# t4_ega_vga.net
KiCad netlist of a schematic drawn in EAGLE
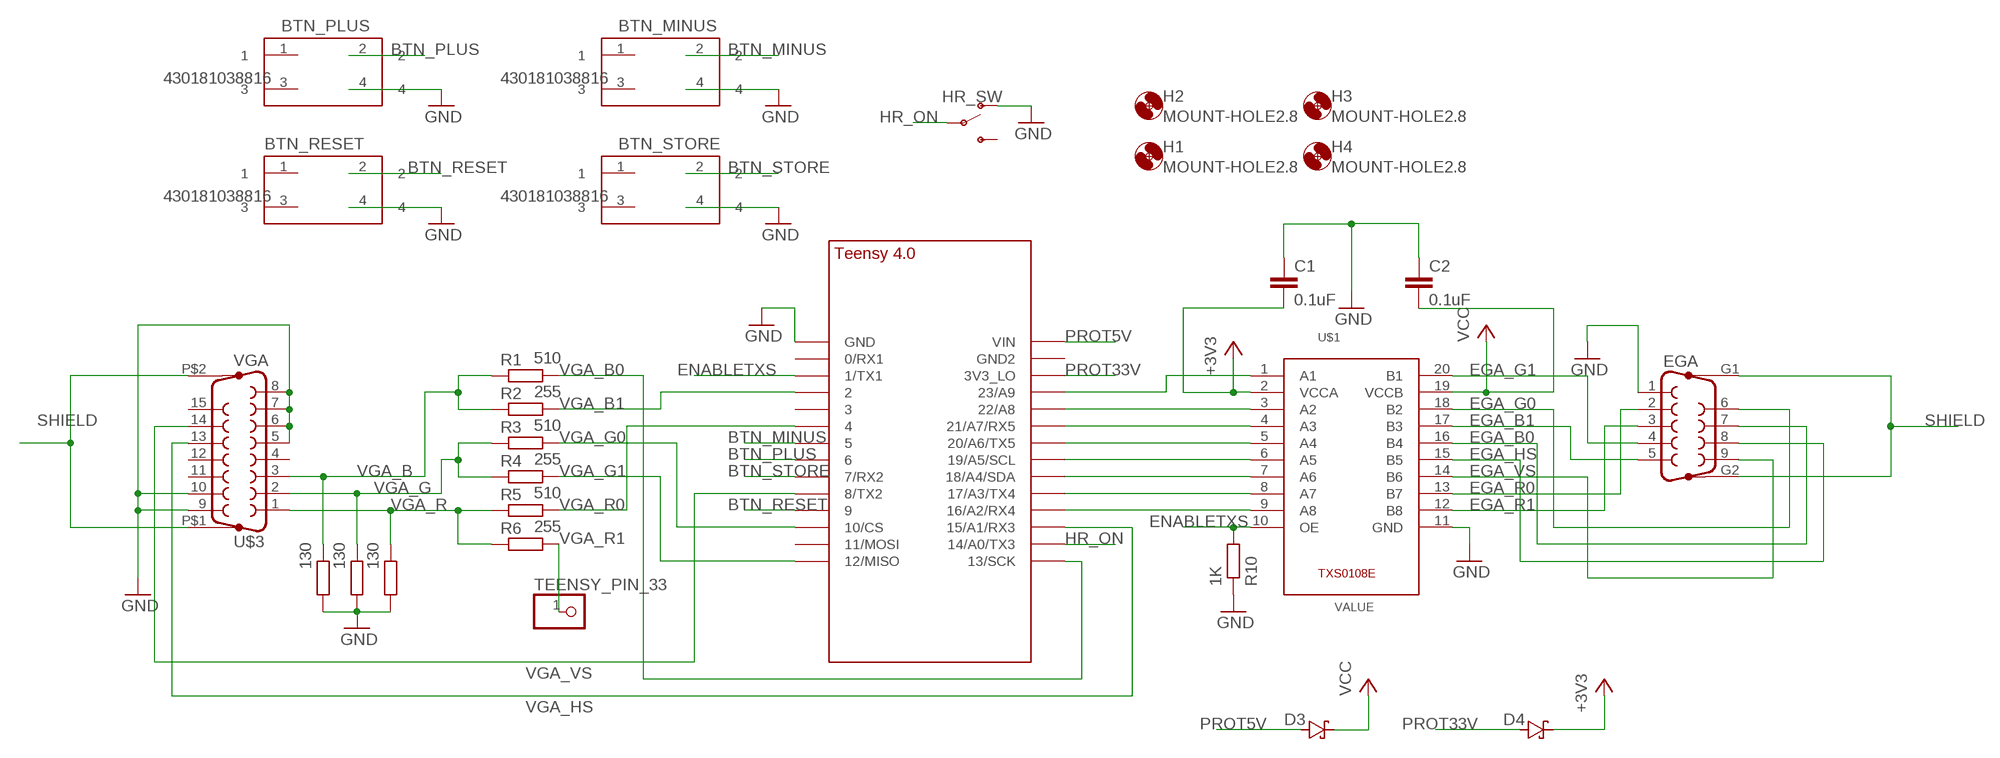
[diagram p0: schematic, sheet 1]

(export (version "E")
  (design (tool "Eeschema 10.0.6"))
  (components
    (comp (ref "BTN_MINUS")
      (value "430181038816")
      (footprint "eagle-import:430181038816")
      (libsource (lib "eagle-import") (part "430181038816"))
    )
    (comp (ref "BTN_PLUS")
      (value "430181038816")
      (footprint "eagle-import:430181038816")
      (libsource (lib "eagle-import") (part "430181038816"))
    )
    (comp (ref "BTN_RESET")
      (value "430181038816")
      (footprint "eagle-import:430181038816")
      (libsource (lib "eagle-import") (part "430181038816"))
    )
    (comp (ref "BTN_STORE")
      (value "430181038816")
      (footprint "eagle-import:430181038816")
      (libsource (lib "eagle-import") (part "430181038816"))
    )
    (comp (ref "C1")
      (value "0.1uF")
      (footprint "eagle-import:C0603")
      (libsource (lib "eagle-import") (part "C-EUC0603"))
    )
    (comp (ref "C2")
      (value "0.1uF")
      (footprint "eagle-import:C0603")
      (libsource (lib "eagle-import") (part "C-EUC0603"))
    )
    (comp (ref "D3")
      (value "SMA-SS34-SYMBOL")
      (footprint "eagle-import:SMA-SS34")
      (libsource (lib "eagle-import") (part "SMA-SS34-SYMBOL"))
    )
    (comp (ref "D4")
      (value "SMA-SS34-SYMBOL")
      (footprint "eagle-import:SMA-SS34")
      (libsource (lib "eagle-import") (part "SMA-SS34-SYMBOL"))
    )
    (comp (ref "EGA")
      (value "F09HP")
      (footprint "eagle-import:F09HP")
      (libsource (lib "eagle-import") (part "F09HP"))
    )
    (comp (ref "H1")
      (value "MOUNT-HOLE2.8")
      (footprint "eagle-import:2,8")
      (libsource (lib "eagle-import") (part "MOUNT-HOLE2.8"))
    )
    (comp (ref "H2")
      (value "MOUNT-HOLE2.8")
      (footprint "eagle-import:2,8")
      (libsource (lib "eagle-import") (part "MOUNT-HOLE2.8"))
    )
    (comp (ref "H3")
      (value "MOUNT-HOLE2.8")
      (footprint "eagle-import:2,8")
      (libsource (lib "eagle-import") (part "MOUNT-HOLE2.8"))
    )
    (comp (ref "H4")
      (value "MOUNT-HOLE2.8")
      (footprint "eagle-import:2,8")
      (libsource (lib "eagle-import") (part "MOUNT-HOLE2.8"))
    )
    (comp (ref "HR_SW")
      (value "SWITCH-SPDT-SMD-RIGHT-ANGLE")
      (footprint "eagle-import:SWITCH_SPST_SMD_A")
      (libsource (lib "eagle-import") (part "SWITCH-SPDT-SMD-RIGHT-ANGLE"))
    )
    (comp (ref "R1")
      (value "510")
      (footprint "eagle-import:R0603")
      (libsource (lib "eagle-import") (part "R-EU_R0603"))
    )
    (comp (ref "R2")
      (value "255")
      (footprint "eagle-import:R0603")
      (libsource (lib "eagle-import") (part "R-EU_R0603"))
    )
    (comp (ref "R3")
      (value "510")
      (footprint "eagle-import:R0603")
      (libsource (lib "eagle-import") (part "R-EU_R0603"))
    )
    (comp (ref "R4")
      (value "255")
      (footprint "eagle-import:R0603")
      (libsource (lib "eagle-import") (part "R-EU_R0603"))
    )
    (comp (ref "R5")
      (value "510")
      (footprint "eagle-import:R0603")
      (libsource (lib "eagle-import") (part "R-EU_R0603"))
    )
    (comp (ref "R6")
      (value "255")
      (footprint "eagle-import:R0603")
      (libsource (lib "eagle-import") (part "R-EU_R0603"))
    )
    (comp (ref "R7")
      (value "130")
      (footprint "eagle-import:R0603")
      (libsource (lib "eagle-import") (part "R-EU_R0603"))
    )
    (comp (ref "R8")
      (value "130")
      (footprint "eagle-import:R0603")
      (libsource (lib "eagle-import") (part "R-EU_R0603"))
    )
    (comp (ref "R9")
      (value "130")
      (footprint "eagle-import:R0603")
      (libsource (lib "eagle-import") (part "R-EU_R0603"))
    )
    (comp (ref "R10")
      (value "1K")
      (footprint "eagle-import:R0603")
      (libsource (lib "eagle-import") (part "R-EU_R0603"))
    )
    (comp (ref "TEENSY_PIN_33")
      (value "PINHD-1X1")
      (footprint "eagle-import:1X01")
      (libsource (lib "eagle-import") (part "PINHD-1X1"))
    )
    (comp (ref "U$1")
      (value "TXS0108E")
      (footprint "eagle-import:TSSOP20")
      (libsource (lib "eagle-import") (part "TXS0108E"))
    )
    (comp (ref "U$3")
      (value "VGA")
      (footprint "eagle-import:HDF15H")
      (libsource (lib "eagle-import") (part "VGA"))
    )
    (comp (ref "U2")
      (value "TEENSY_4.0-BASIC")
      (footprint "eagle-import:TEENSY_4.0-BASIC")
      (libsource (lib "eagle-import") (part "TEENSY_4.0-BASIC"))
    )
  )
  (nets
    (net (code "1") (name "+3V3") (class "Default")
      (node (ref "C1") (pin "2") (pinfunction "2_2") (pintype "passive"))
      (node (ref "D4") (pin "2") (pinfunction "K_2") (pintype "passive"))
      (node (ref "U$1") (pin "2") (pinfunction "VCCA_2") (pintype "bidirectional"))
    )
    (net (code "2") (name "/BTN_MINUS") (class "Default")
      (node (ref "BTN_MINUS") (pin "2") (pinfunction "2_2") (pintype "bidirectional"))
      (node (ref "U2") (pin "5") (pinfunction "5_5") (pintype "bidirectional"))
    )
    (net (code "3") (name "/BTN_PLUS") (class "Default")
      (node (ref "BTN_PLUS") (pin "2") (pinfunction "2_2") (pintype "bidirectional"))
      (node (ref "U2") (pin "6") (pinfunction "6_6") (pintype "bidirectional"))
    )
    (net (code "4") (name "/BTN_RESET") (class "Default")
      (node (ref "BTN_RESET") (pin "2") (pinfunction "2_2") (pintype "bidirectional"))
      (node (ref "U2") (pin "9/CS") (pinfunction "9_9/CS") (pintype "bidirectional"))
    )
    (net (code "5") (name "/BTN_STORE") (class "Default")
      (node (ref "BTN_STORE") (pin "2") (pinfunction "2_2") (pintype "bidirectional"))
      (node (ref "U2") (pin "7") (pinfunction "7/RX2_7") (pintype "bidirectional"))
    )
    (net (code "6") (name "/EGA_B0") (class "Default")
      (node (ref "EGA") (pin "7") (pinfunction "7_7") (pintype "passive"))
      (node (ref "U$1") (pin "16") (pinfunction "B4_16") (pintype "bidirectional"))
    )
    (net (code "7") (name "/EGA_B1") (class "Default")
      (node (ref "EGA") (pin "5") (pinfunction "5_5") (pintype "passive"))
      (node (ref "U$1") (pin "17") (pinfunction "B3_17") (pintype "bidirectional"))
    )
    (net (code "8") (name "/EGA_G0") (class "Default")
      (node (ref "EGA") (pin "6") (pinfunction "6_6") (pintype "passive"))
      (node (ref "U$1") (pin "18") (pinfunction "B2_18") (pintype "bidirectional"))
    )
    (net (code "9") (name "/EGA_G1") (class "Default")
      (node (ref "EGA") (pin "4") (pinfunction "4_4") (pintype "passive"))
      (node (ref "U$1") (pin "20") (pinfunction "B1_20") (pintype "bidirectional"))
    )
    (net (code "10") (name "/EGA_HS") (class "Default")
      (node (ref "EGA") (pin "8") (pinfunction "8_8") (pintype "passive"))
      (node (ref "U$1") (pin "15") (pinfunction "B5_15") (pintype "bidirectional"))
    )
    (net (code "11") (name "/EGA_R0") (class "Default")
      (node (ref "EGA") (pin "2") (pinfunction "2_2") (pintype "passive"))
      (node (ref "U$1") (pin "13") (pinfunction "B7_13") (pintype "bidirectional"))
    )
    (net (code "12") (name "/EGA_R1") (class "Default")
      (node (ref "EGA") (pin "3") (pinfunction "3_3") (pintype "passive"))
      (node (ref "U$1") (pin "12") (pinfunction "B8_12") (pintype "bidirectional"))
    )
    (net (code "13") (name "/EGA_VS") (class "Default")
      (node (ref "EGA") (pin "9") (pinfunction "9_9") (pintype "passive"))
      (node (ref "U$1") (pin "14") (pinfunction "B6_14") (pintype "bidirectional"))
    )
    (net (code "14") (name "/ENABLETXS") (class "Default")
      (node (ref "R10") (pin "2") (pinfunction "2_2") (pintype "passive"))
      (node (ref "U$1") (pin "10") (pinfunction "OE_10") (pintype "bidirectional"))
      (node (ref "U2") (pin "1/TX") (pinfunction "1/TX1_1/TX") (pintype "bidirectional"))
    )
    (net (code "15") (name "/HR_ON") (class "Default")
      (node (ref "HR_SW") (pin "2") (pinfunction "P_2") (pintype "passive"))
      (node (ref "U2") (pin "14/A0") (pinfunction "14/A0/TX3_14/A0") (pintype "bidirectional"))
    )
    (net (code "16") (name "/PROT5V") (class "Default")
      (node (ref "D3") (pin "1") (pinfunction "A_1") (pintype "passive"))
      (node (ref "U2") (pin "VIN") (pinfunction "VIN_VIN") (pintype "bidirectional"))
    )
    (net (code "17") (name "/PROT33V") (class "Default")
      (node (ref "D4") (pin "1") (pinfunction "A_1") (pintype "passive"))
      (node (ref "U2") (pin "3V3_LO") (pinfunction "3V3_LO_3V3_LO") (pintype "bidirectional"))
    )
    (net (code "18") (name "/SHIELD") (class "Default")
      (node (ref "EGA") (pin "G1") (pinfunction "G1_G1") (pintype "passive"))
      (node (ref "EGA") (pin "G2") (pinfunction "G2_G2") (pintype "passive"))
      (node (ref "U$3") (pin "P$1") (pinfunction "G1_P$1") (pintype "passive"))
      (node (ref "U$3") (pin "P$2") (pinfunction "G2_P$2") (pintype "passive"))
    )
    (net (code "19") (name "/VGA_B") (class "Default")
      (node (ref "R1") (pin "1") (pinfunction "1_1") (pintype "passive"))
      (node (ref "R2") (pin "1") (pinfunction "1_1") (pintype "passive"))
      (node (ref "R7") (pin "2") (pinfunction "2_2") (pintype "passive"))
      (node (ref "U$3") (pin "3") (pinfunction "3_3") (pintype "passive"))
    )
    (net (code "20") (name "/VGA_B0") (class "Default")
      (node (ref "R1") (pin "2") (pinfunction "2_2") (pintype "passive"))
      (node (ref "U2") (pin "13/SCK") (pinfunction "13/SCK_13/SCK") (pintype "bidirectional"))
    )
    (net (code "21") (name "/VGA_B1") (class "Default")
      (node (ref "R2") (pin "2") (pinfunction "2_2") (pintype "passive"))
      (node (ref "U2") (pin "2") (pinfunction "2_2") (pintype "bidirectional"))
    )
    (net (code "22") (name "/VGA_G") (class "Default")
      (node (ref "R3") (pin "1") (pinfunction "1_1") (pintype "passive"))
      (node (ref "R4") (pin "1") (pinfunction "1_1") (pintype "passive"))
      (node (ref "R8") (pin "2") (pinfunction "2_2") (pintype "passive"))
      (node (ref "U$3") (pin "2") (pinfunction "2_2") (pintype "passive"))
    )
    (net (code "23") (name "/VGA_G0") (class "Default")
      (node (ref "R3") (pin "2") (pinfunction "2_2") (pintype "passive"))
      (node (ref "U2") (pin "10/CS") (pinfunction "10/CS_10/CS") (pintype "bidirectional"))
    )
    (net (code "24") (name "/VGA_G1") (class "Default")
      (node (ref "R4") (pin "2") (pinfunction "2_2") (pintype "passive"))
      (node (ref "U2") (pin "12/MISO") (pinfunction "12/MISO_12/MISO") (pintype "bidirectional"))
    )
    (net (code "25") (name "/VGA_HS") (class "Default")
      (node (ref "U$3") (pin "13") (pinfunction "13_13") (pintype "passive"))
      (node (ref "U2") (pin "15/A1") (pinfunction "15/A1/RX3_15/A1") (pintype "bidirectional"))
    )
    (net (code "26") (name "/VGA_R") (class "Default")
      (node (ref "R5") (pin "1") (pinfunction "1_1") (pintype "passive"))
      (node (ref "R6") (pin "1") (pinfunction "1_1") (pintype "passive"))
      (node (ref "R9") (pin "2") (pinfunction "2_2") (pintype "passive"))
      (node (ref "U$3") (pin "1") (pinfunction "1_1") (pintype "passive"))
    )
    (net (code "27") (name "/VGA_R0") (class "Default")
      (node (ref "R5") (pin "2") (pinfunction "2_2") (pintype "passive"))
      (node (ref "U2") (pin "4/CANRX") (pinfunction "4_4/CANRX") (pintype "bidirectional"))
    )
    (net (code "28") (name "/VGA_R1") (class "Default")
      (node (ref "R6") (pin "2") (pinfunction "2_2") (pintype "passive"))
      (node (ref "TEENSY_PIN_33") (pin "1") (pinfunction "1_1") (pintype "passive"))
    )
    (net (code "29") (name "/VGA_VS") (class "Default")
      (node (ref "U$3") (pin "14") (pinfunction "14_14") (pintype "passive"))
      (node (ref "U2") (pin "8") (pinfunction "8/TX2_8") (pintype "bidirectional"))
    )
    (net (code "30") (name "GND") (class "Default")
      (node (ref "BTN_MINUS") (pin "4") (pinfunction "4_4") (pintype "bidirectional"))
      (node (ref "BTN_PLUS") (pin "4") (pinfunction "4_4") (pintype "bidirectional"))
      (node (ref "BTN_RESET") (pin "4") (pinfunction "4_4") (pintype "bidirectional"))
      (node (ref "BTN_STORE") (pin "4") (pinfunction "4_4") (pintype "bidirectional"))
      (node (ref "C1") (pin "1") (pinfunction "1_1") (pintype "passive"))
      (node (ref "C2") (pin "1") (pinfunction "1_1") (pintype "passive"))
      (node (ref "EGA") (pin "1") (pinfunction "1_1") (pintype "passive"))
      (node (ref "HR_SW") (pin "1") (pinfunction "O_1") (pintype "passive"))
      (node (ref "R10") (pin "1") (pinfunction "1_1") (pintype "passive"))
      (node (ref "R7") (pin "1") (pinfunction "1_1") (pintype "passive"))
      (node (ref "R8") (pin "1") (pinfunction "1_1") (pintype "passive"))
      (node (ref "R9") (pin "1") (pinfunction "1_1") (pintype "passive"))
      (node (ref "U$1") (pin "11") (pinfunction "GND_11") (pintype "bidirectional"))
      (node (ref "U$3") (pin "10") (pinfunction "10_10") (pintype "passive"))
      (node (ref "U$3") (pin "5") (pinfunction "5_5") (pintype "passive"))
      (node (ref "U$3") (pin "6") (pinfunction "6_6") (pintype "passive"))
      (node (ref "U$3") (pin "7") (pinfunction "7_7") (pintype "passive"))
      (node (ref "U$3") (pin "8") (pinfunction "8_8") (pintype "passive"))
      (node (ref "U$3") (pin "9") (pinfunction "9_9") (pintype "passive"))
      (node (ref "U2") (pin "GND") (pinfunction "GND_GND") (pintype "bidirectional"))
    )
    (net (code "31") (name "Net-(U$1-A1)") (class "Default")
      (node (ref "U$1") (pin "1") (pinfunction "A1_1") (pintype "bidirectional"))
      (node (ref "U2") (pin "23/A9") (pinfunction "23/A9_23/A9") (pintype "bidirectional"))
    )
    (net (code "32") (name "Net-(U$1-A2)") (class "Default")
      (node (ref "U$1") (pin "3") (pinfunction "A2_3") (pintype "bidirectional"))
      (node (ref "U2") (pin "22/A8") (pinfunction "22/A8_22/A8") (pintype "bidirectional"))
    )
    (net (code "33") (name "Net-(U$1-A3)") (class "Default")
      (node (ref "U$1") (pin "4") (pinfunction "A3_4") (pintype "bidirectional"))
      (node (ref "U2") (pin "21/A7") (pinfunction "21/A7/RX5_21/A7") (pintype "bidirectional"))
    )
    (net (code "34") (name "Net-(U$1-A4)") (class "Default")
      (node (ref "U$1") (pin "5") (pinfunction "A4_5") (pintype "bidirectional"))
      (node (ref "U2") (pin "20/A6") (pinfunction "20/A6/TX5_20/A6") (pintype "bidirectional"))
    )
    (net (code "35") (name "Net-(U$1-A5)") (class "Default")
      (node (ref "U$1") (pin "6") (pinfunction "A5_6") (pintype "bidirectional"))
      (node (ref "U2") (pin "19/A5/SCL") (pinfunction "19/A5/SCL_19/A5/SCL") (pintype "bidirectional"))
    )
    (net (code "36") (name "Net-(U$1-A6)") (class "Default")
      (node (ref "U$1") (pin "7") (pinfunction "A6_7") (pintype "bidirectional"))
      (node (ref "U2") (pin "18/A4/SDA") (pinfunction "18/A4/SDA_18/A4/SDA") (pintype "bidirectional"))
    )
    (net (code "37") (name "Net-(U$1-A7)") (class "Default")
      (node (ref "U$1") (pin "8") (pinfunction "A7_8") (pintype "bidirectional"))
      (node (ref "U2") (pin "17/A3") (pinfunction "17/A3/TX4_17/A3") (pintype "bidirectional"))
    )
    (net (code "38") (name "Net-(U$1-A8)") (class "Default")
      (node (ref "U$1") (pin "9") (pinfunction "A8_9") (pintype "bidirectional"))
      (node (ref "U2") (pin "16/A2") (pinfunction "16/A2/RX4_16/A2") (pintype "bidirectional"))
    )
    (net (code "39") (name "VCC") (class "Default")
      (node (ref "C2") (pin "2") (pinfunction "2_2") (pintype "passive"))
      (node (ref "D3") (pin "2") (pinfunction "K_2") (pintype "passive"))
      (node (ref "U$1") (pin "19") (pinfunction "VCCB_19") (pintype "bidirectional"))
    )
    (net (code "40") (name "unconnected-(BTN_MINUS-Pad1)") (class "Default")
      (node (ref "BTN_MINUS") (pin "1") (pinfunction "1_1") (pintype "bidirectional"))
    )
    (net (code "41") (name "unconnected-(BTN_MINUS-Pad3)") (class "Default")
      (node (ref "BTN_MINUS") (pin "3") (pinfunction "3_3") (pintype "bidirectional"))
    )
    (net (code "42") (name "unconnected-(BTN_PLUS-Pad1)") (class "Default")
      (node (ref "BTN_PLUS") (pin "1") (pinfunction "1_1") (pintype "bidirectional"))
    )
    (net (code "43") (name "unconnected-(BTN_PLUS-Pad3)") (class "Default")
      (node (ref "BTN_PLUS") (pin "3") (pinfunction "3_3") (pintype "bidirectional"))
    )
    (net (code "44") (name "unconnected-(BTN_RESET-Pad1)") (class "Default")
      (node (ref "BTN_RESET") (pin "1") (pinfunction "1_1") (pintype "bidirectional"))
    )
    (net (code "45") (name "unconnected-(BTN_RESET-Pad3)") (class "Default")
      (node (ref "BTN_RESET") (pin "3") (pinfunction "3_3") (pintype "bidirectional"))
    )
    (net (code "46") (name "unconnected-(BTN_STORE-Pad1)") (class "Default")
      (node (ref "BTN_STORE") (pin "1") (pinfunction "1_1") (pintype "bidirectional"))
    )
    (net (code "47") (name "unconnected-(BTN_STORE-Pad3)") (class "Default")
      (node (ref "BTN_STORE") (pin "3") (pinfunction "3_3") (pintype "bidirectional"))
    )
    (net (code "48") (name "unconnected-(HR_SW-S-Pad3)") (class "Default")
      (node (ref "HR_SW") (pin "3") (pinfunction "S_3") (pintype "passive"))
    )
    (net (code "49") (name "unconnected-(U$3-Pad4)") (class "Default")
      (node (ref "U$3") (pin "4") (pinfunction "4_4") (pintype "passive"))
    )
    (net (code "50") (name "unconnected-(U$3-Pad11)") (class "Default")
      (node (ref "U$3") (pin "11") (pinfunction "11_11") (pintype "passive"))
    )
    (net (code "51") (name "unconnected-(U$3-Pad12)") (class "Default")
      (node (ref "U$3") (pin "12") (pinfunction "12_12") (pintype "passive"))
    )
    (net (code "52") (name "unconnected-(U$3-Pad15)") (class "Default")
      (node (ref "U$3") (pin "15") (pinfunction "15_15") (pintype "passive"))
    )
    (net (code "53") (name "unconnected-(U2-0{slash}RX1-Pad0{slash}RX)") (class "Default")
      (node (ref "U2") (pin "0/RX") (pinfunction "0/RX1_0/RX") (pintype "bidirectional"))
    )
    (net (code "54") (name "unconnected-(U2-3-Pad3{slash}CANTX)") (class "Default")
      (node (ref "U2") (pin "3/CANTX") (pinfunction "3_3/CANTX") (pintype "bidirectional"))
    )
    (net (code "55") (name "unconnected-(U2-Pad11{slash}MOSI)") (class "Default")
      (node (ref "U2") (pin "11/MOSI") (pinfunction "11/MOSI_11/MOSI") (pintype "bidirectional"))
    )
    (net (code "56") (name "unconnected-(U2-PadGND2)") (class "Default")
      (node (ref "U2") (pin "GND2") (pinfunction "GND2_GND2") (pintype "bidirectional"))
    )
  )
)
